# UKHASnet-avr-sensor.net
KiCad netlist of a schematic drawn in EAGLE
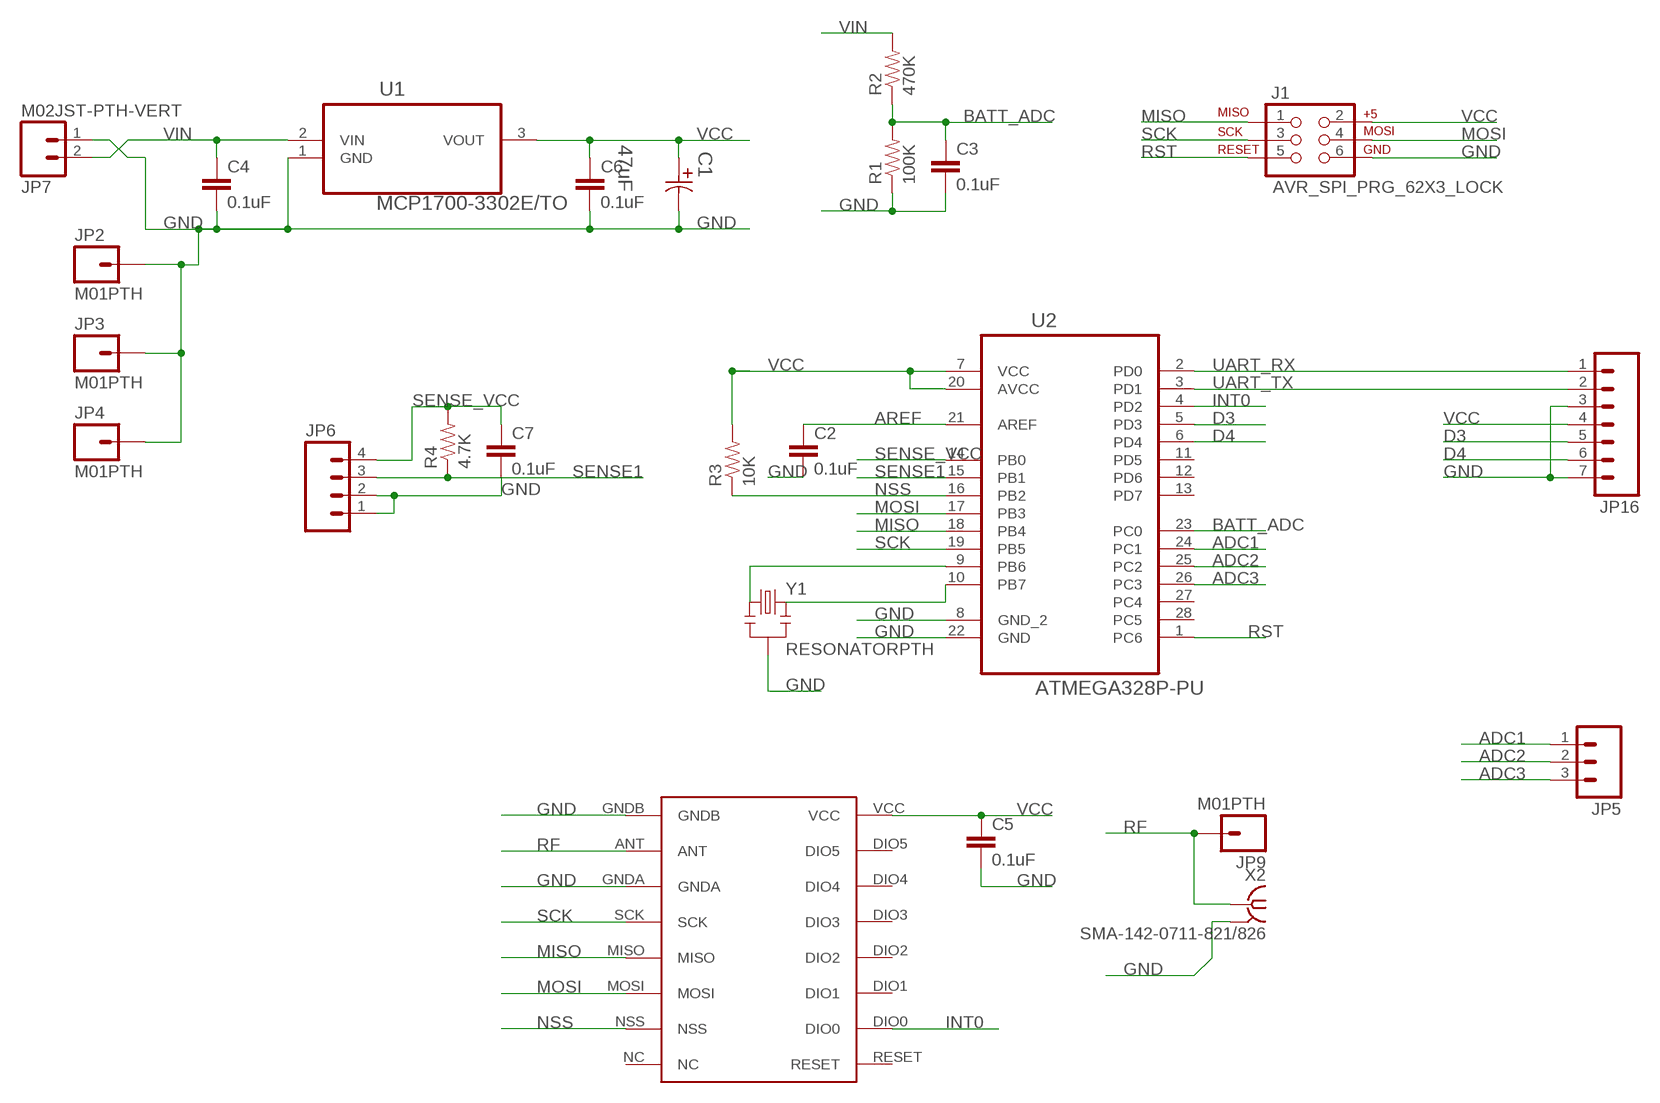
[diagram p0: schematic, sheet 1]

(export (version "E")
  (design (tool "Eeschema 10.0.6"))
  (components
    (comp (ref "C1")
      (value "47uF")
      (footprint "eagle-import:CAPPR150-400X1200")
      (fields (field (name "MPN") "EEUFC1J6R8") (field (name "TOLERANCE") "±20 %"))
      (libsource (lib "eagle-import") (part "EEU-P1.5FC1J6R8"))
    )
    (comp (ref "C2")
      (value "0.1uF")
      (footprint "eagle-import:C2.5-2")
      (libsource (lib "eagle-import") (part "C2.5/2"))
    )
    (comp (ref "C3")
      (value "0.1uF")
      (footprint "eagle-import:C2.5-2")
      (libsource (lib "eagle-import") (part "C2.5/2"))
    )
    (comp (ref "C4")
      (value "0.1uF")
      (footprint "eagle-import:C2.5-2")
      (libsource (lib "eagle-import") (part "C2.5/2"))
    )
    (comp (ref "C5")
      (value "0.1uF")
      (footprint "eagle-import:C2.5-2")
      (libsource (lib "eagle-import") (part "C2.5/2"))
    )
    (comp (ref "C6")
      (value "0.1uF")
      (footprint "eagle-import:C2.5-2")
      (libsource (lib "eagle-import") (part "C2.5/2"))
    )
    (comp (ref "C7")
      (value "0.1uF")
      (footprint "eagle-import:C2.5-2")
      (libsource (lib "eagle-import") (part "C2.5/2"))
    )
    (comp (ref "J1")
      (value "AVR_SPI_PRG_62X3_LOCK")
      (footprint "eagle-import:2X3_LOCK")
      (libsource (lib "eagle-import") (part "AVR_SPI_PRG_62X3_LOCK"))
    )
    (comp (ref "JP2")
      (value "M01PTH")
      (footprint "eagle-import:1X01")
      (libsource (lib "eagle-import") (part "M01PTH"))
    )
    (comp (ref "JP3")
      (value "M01PTH")
      (footprint "eagle-import:1X01")
      (libsource (lib "eagle-import") (part "M01PTH"))
    )
    (comp (ref "JP4")
      (value "M01PTH")
      (footprint "eagle-import:1X01")
      (libsource (lib "eagle-import") (part "M01PTH"))
    )
    (comp (ref "JP5")
      (value "M03PTH")
      (footprint "eagle-import:1X03")
      (libsource (lib "eagle-import") (part "M03PTH"))
    )
    (comp (ref "JP6")
      (value "M04PTH")
      (footprint "eagle-import:1X04")
      (libsource (lib "eagle-import") (part "M04PTH"))
    )
    (comp (ref "JP7")
      (value "M02JST-PTH-VERT")
      (footprint "eagle-import:JST-2-PTH-VERT")
      (libsource (lib "eagle-import") (part "M02JST-PTH-VERT"))
    )
    (comp (ref "JP9")
      (value "M01PTH")
      (footprint "eagle-import:1X01")
      (libsource (lib "eagle-import") (part "M01PTH"))
    )
    (comp (ref "JP16")
      (value "M07")
      (footprint "eagle-import:1X07")
      (libsource (lib "eagle-import") (part "M07"))
    )
    (comp (ref "R1")
      (value "100K")
      (footprint "eagle-import:AXIAL-0.4")
      (libsource (lib "eagle-import") (part "RESISTORPTH-1/4W"))
    )
    (comp (ref "R2")
      (value "470K")
      (footprint "eagle-import:AXIAL-0.4")
      (libsource (lib "eagle-import") (part "RESISTORPTH-1/4W"))
    )
    (comp (ref "R3")
      (value "10K")
      (footprint "eagle-import:AXIAL-0.4")
      (libsource (lib "eagle-import") (part "RESISTORPTH-1/4W"))
    )
    (comp (ref "R4")
      (value "4.7K")
      (footprint "eagle-import:AXIAL-0.4")
      (libsource (lib "eagle-import") (part "RESISTORPTH-1/4W"))
    )
    (comp (ref "U$1")
      (value "RFM69HW")
      (footprint "eagle-import:RFM")
      (libsource (lib "eagle-import") (part "RFM69HW"))
    )
    (comp (ref "U1")
      (value "MCP1700-3302E/TO")
      (footprint "eagle-import:TO127P254X495-3")
      (libsource (lib "eagle-import") (part "MCP1700-3302E/TO"))
    )
    (comp (ref "U2")
      (value "ATMEGA328P-PU")
      (footprint "eagle-import:DIP254P762X457-28")
      (libsource (lib "eagle-import") (part "ATMEGA328P-PU"))
    )
    (comp (ref "X2")
      (value "SMA-142-0711-821/826")
      (footprint "eagle-import:J502-ND-142-0711-821_826")
      (fields (field (name "MF") "JOHNSON COMPONENTS") (field (name "MPN") "142-0711-821"))
      (libsource (lib "eagle-import") (part "SMA-142-0711-821/826"))
    )
    (comp (ref "Y1")
      (value "RESONATORPTH")
      (footprint "eagle-import:RESONATOR-PTH")
      (libsource (lib "eagle-import") (part "RESONATORPTH"))
    )
  )
  (nets
    (net (code "1") (name "/ADC1") (class "Default")
      (node (ref "JP5") (pin "1") (pinfunction "1_1") (pintype "passive"))
      (node (ref "U2") (pin "24") (pinfunction "PC1_24") (pintype "bidirectional"))
    )
    (net (code "2") (name "/ADC2") (class "Default")
      (node (ref "JP5") (pin "2") (pinfunction "2_2") (pintype "passive"))
      (node (ref "U2") (pin "25") (pinfunction "PC2_25") (pintype "bidirectional"))
    )
    (net (code "3") (name "/ADC3") (class "Default")
      (node (ref "JP5") (pin "3") (pinfunction "3_3") (pintype "passive"))
      (node (ref "U2") (pin "26") (pinfunction "PC3_26") (pintype "bidirectional"))
    )
    (net (code "4") (name "/AREF") (class "Default")
      (node (ref "C2") (pin "1") (pinfunction "1_1") (pintype "passive"))
      (node (ref "U2") (pin "21") (pinfunction "AREF_21") (pintype "input"))
    )
    (net (code "5") (name "/BATT_ADC") (class "Default")
      (node (ref "C3") (pin "1") (pinfunction "1_1") (pintype "passive"))
      (node (ref "R1") (pin "P$2") (pinfunction "2_P$2") (pintype "passive"))
      (node (ref "R2") (pin "P$1") (pinfunction "1_P$1") (pintype "passive"))
      (node (ref "U2") (pin "23") (pinfunction "PC0_23") (pintype "bidirectional"))
    )
    (net (code "6") (name "/D3") (class "Default")
      (node (ref "JP16") (pin "5") (pinfunction "5_5") (pintype "passive"))
      (node (ref "U2") (pin "5") (pinfunction "PD3_5") (pintype "bidirectional"))
    )
    (net (code "7") (name "/D4") (class "Default")
      (node (ref "JP16") (pin "6") (pinfunction "6_6") (pintype "passive"))
      (node (ref "U2") (pin "6") (pinfunction "PD4_6") (pintype "bidirectional"))
    )
    (net (code "8") (name "/GND") (class "Default")
      (node (ref "C1") (pin "2") (pinfunction "2_2") (pintype "passive"))
      (node (ref "C2") (pin "2") (pinfunction "2_2") (pintype "passive"))
      (node (ref "C3") (pin "2") (pinfunction "2_2") (pintype "passive"))
      (node (ref "C4") (pin "2") (pinfunction "2_2") (pintype "passive"))
      (node (ref "C5") (pin "2") (pinfunction "2_2") (pintype "passive"))
      (node (ref "C6") (pin "2") (pinfunction "2_2") (pintype "passive"))
      (node (ref "C7") (pin "2") (pinfunction "2_2") (pintype "passive"))
      (node (ref "J1") (pin "6") (pinfunction "6_6") (pintype "passive"))
      (node (ref "JP16") (pin "3") (pinfunction "3_3") (pintype "passive"))
      (node (ref "JP16") (pin "7") (pinfunction "7_7") (pintype "passive"))
      (node (ref "JP2") (pin "1") (pinfunction "1_1") (pintype "passive"))
      (node (ref "JP3") (pin "1") (pinfunction "1_1") (pintype "passive"))
      (node (ref "JP4") (pin "1") (pinfunction "1_1") (pintype "passive"))
      (node (ref "JP6") (pin "1") (pinfunction "1_1") (pintype "passive"))
      (node (ref "JP6") (pin "2") (pinfunction "2_2") (pintype "passive"))
      (node (ref "JP7") (pin "1") (pinfunction "1_1") (pintype "passive"))
      (node (ref "R1") (pin "P$1") (pinfunction "1_P$1") (pintype "passive"))
      (node (ref "U$1") (pin "GNDA") (pinfunction "GNDA_GNDA") (pintype "bidirectional"))
      (node (ref "U$1") (pin "GNDB") (pinfunction "GNDB_GNDB") (pintype "bidirectional"))
      (node (ref "U1") (pin "1") (pinfunction "GND_1") (pintype "passive"))
      (node (ref "U2") (pin "22") (pinfunction "GND_22") (pintype "passive"))
      (node (ref "U2") (pin "8") (pinfunction "GND_2_8") (pintype "passive"))
      (node (ref "X2") (pin "G@1") (pinfunction "2_G@1") (pintype "passive"))
      (node (ref "X2") (pin "G@2") (pinfunction "2_G@2") (pintype "passive"))
      (node (ref "X2") (pin "G@3") (pinfunction "2_G@3") (pintype "passive"))
      (node (ref "X2") (pin "G@4") (pinfunction "2_G@4") (pintype "passive"))
      (node (ref "Y1") (pin "2") (pinfunction "2_2") (pintype "passive"))
    )
    (net (code "9") (name "/INT0") (class "Default")
      (node (ref "U$1") (pin "DIO0") (pinfunction "DIO0_DIO0") (pintype "bidirectional"))
      (node (ref "U2") (pin "4") (pinfunction "PD2_4") (pintype "bidirectional"))
    )
    (net (code "10") (name "/MISO") (class "Default")
      (node (ref "J1") (pin "1") (pinfunction "1_1") (pintype "passive"))
      (node (ref "U$1") (pin "MISO") (pinfunction "MISO_MISO") (pintype "bidirectional"))
      (node (ref "U2") (pin "18") (pinfunction "PB4_18") (pintype "bidirectional"))
    )
    (net (code "11") (name "/MOSI") (class "Default")
      (node (ref "J1") (pin "4") (pinfunction "4_4") (pintype "passive"))
      (node (ref "U$1") (pin "MOSI") (pinfunction "MOSI_MOSI") (pintype "bidirectional"))
      (node (ref "U2") (pin "17") (pinfunction "PB3_17") (pintype "bidirectional"))
    )
    (net (code "12") (name "/NSS") (class "Default")
      (node (ref "R3") (pin "P$1") (pinfunction "1_P$1") (pintype "passive"))
      (node (ref "U$1") (pin "NSS") (pinfunction "NSS_NSS") (pintype "bidirectional"))
      (node (ref "U2") (pin "16") (pinfunction "PB2_16") (pintype "bidirectional"))
    )
    (net (code "13") (name "/RF") (class "Default")
      (node (ref "JP9") (pin "1") (pinfunction "1_1") (pintype "passive"))
      (node (ref "U$1") (pin "ANT") (pinfunction "ANT_ANT") (pintype "bidirectional"))
      (node (ref "X2") (pin "1") (pinfunction "1_1") (pintype "passive"))
    )
    (net (code "14") (name "/RST") (class "Default")
      (node (ref "J1") (pin "5") (pinfunction "5_5") (pintype "passive"))
      (node (ref "U2") (pin "1") (pinfunction "PC6_1") (pintype "bidirectional"))
    )
    (net (code "15") (name "/SCK") (class "Default")
      (node (ref "J1") (pin "3") (pinfunction "3_3") (pintype "passive"))
      (node (ref "U$1") (pin "SCK") (pinfunction "SCK_SCK") (pintype "bidirectional"))
      (node (ref "U2") (pin "19") (pinfunction "PB5_19") (pintype "bidirectional"))
    )
    (net (code "16") (name "/SENSE1") (class "Default")
      (node (ref "JP6") (pin "3") (pinfunction "3_3") (pintype "passive"))
      (node (ref "R4") (pin "P$1") (pinfunction "1_P$1") (pintype "passive"))
      (node (ref "U2") (pin "15") (pinfunction "PB1_15") (pintype "bidirectional"))
    )
    (net (code "17") (name "/SENSE_VCC") (class "Default")
      (node (ref "C7") (pin "1") (pinfunction "1_1") (pintype "passive"))
      (node (ref "JP6") (pin "4") (pinfunction "4_4") (pintype "passive"))
      (node (ref "R4") (pin "P$2") (pinfunction "2_P$2") (pintype "passive"))
      (node (ref "U2") (pin "14") (pinfunction "PB0_14") (pintype "bidirectional"))
    )
    (net (code "18") (name "/UART_RX") (class "Default")
      (node (ref "JP16") (pin "1") (pinfunction "1_1") (pintype "passive"))
      (node (ref "U2") (pin "2") (pinfunction "PD0_2") (pintype "bidirectional"))
    )
    (net (code "19") (name "/UART_TX") (class "Default")
      (node (ref "JP16") (pin "2") (pinfunction "2_2") (pintype "passive"))
      (node (ref "U2") (pin "3") (pinfunction "PD1_3") (pintype "bidirectional"))
    )
    (net (code "20") (name "/VCC") (class "Default")
      (node (ref "C1") (pin "1") (pinfunction "1_1") (pintype "passive"))
      (node (ref "C5") (pin "1") (pinfunction "1_1") (pintype "passive"))
      (node (ref "C6") (pin "1") (pinfunction "1_1") (pintype "passive"))
      (node (ref "J1") (pin "2") (pinfunction "2_2") (pintype "passive"))
      (node (ref "JP16") (pin "4") (pinfunction "4_4") (pintype "passive"))
      (node (ref "R3") (pin "P$2") (pinfunction "2_P$2") (pintype "passive"))
      (node (ref "U$1") (pin "VCC") (pinfunction "VCC_VCC") (pintype "bidirectional"))
      (node (ref "U1") (pin "3") (pinfunction "VOUT_3") (pintype "output"))
      (node (ref "U2") (pin "20") (pinfunction "AVCC_20") (pintype "power_in"))
      (node (ref "U2") (pin "7") (pinfunction "VCC_7") (pintype "power_in"))
    )
    (net (code "21") (name "/VIN") (class "Default")
      (node (ref "C4") (pin "1") (pinfunction "1_1") (pintype "passive"))
      (node (ref "JP7") (pin "2") (pinfunction "2_2") (pintype "passive"))
      (node (ref "R2") (pin "P$2") (pinfunction "2_P$2") (pintype "passive"))
      (node (ref "U1") (pin "2") (pinfunction "VIN_2") (pintype "input"))
    )
    (net (code "22") (name "Net-(U2-PB6)") (class "Default")
      (node (ref "U2") (pin "9") (pinfunction "PB6_9") (pintype "bidirectional"))
      (node (ref "Y1") (pin "1") (pinfunction "1_1") (pintype "passive"))
    )
    (net (code "23") (name "Net-(U2-PB7)") (class "Default")
      (node (ref "U2") (pin "10") (pinfunction "PB7_10") (pintype "bidirectional"))
      (node (ref "Y1") (pin "3") (pinfunction "3_3") (pintype "passive"))
    )
    (net (code "24") (name "unconnected-(U$1-PadDIO1)") (class "Default")
      (node (ref "U$1") (pin "DIO1") (pinfunction "DIO1_DIO1") (pintype "bidirectional"))
    )
    (net (code "25") (name "unconnected-(U$1-PadDIO2)") (class "Default")
      (node (ref "U$1") (pin "DIO2") (pinfunction "DIO2_DIO2") (pintype "bidirectional"))
    )
    (net (code "26") (name "unconnected-(U$1-PadDIO3)") (class "Default")
      (node (ref "U$1") (pin "DIO3") (pinfunction "DIO3_DIO3") (pintype "bidirectional"))
    )
    (net (code "27") (name "unconnected-(U$1-PadDIO4)") (class "Default")
      (node (ref "U$1") (pin "DIO4") (pinfunction "DIO4_DIO4") (pintype "bidirectional"))
    )
    (net (code "28") (name "unconnected-(U$1-PadDIO5)") (class "Default")
      (node (ref "U$1") (pin "DIO5") (pinfunction "DIO5_DIO5") (pintype "bidirectional"))
    )
    (net (code "29") (name "unconnected-(U$1-PadNC)") (class "Default")
      (node (ref "U$1") (pin "NC") (pinfunction "NC_NC") (pintype "bidirectional"))
    )
    (net (code "30") (name "unconnected-(U$1-PadRESET)") (class "Default")
      (node (ref "U$1") (pin "RESET") (pinfunction "RESET_RESET") (pintype "bidirectional"))
    )
    (net (code "31") (name "unconnected-(U2-PC4-Pad27)") (class "Default")
      (node (ref "U2") (pin "27") (pinfunction "PC4_27") (pintype "bidirectional"))
    )
    (net (code "32") (name "unconnected-(U2-PC5-Pad28)") (class "Default")
      (node (ref "U2") (pin "28") (pinfunction "PC5_28") (pintype "bidirectional"))
    )
    (net (code "33") (name "unconnected-(U2-PD5-Pad11)") (class "Default")
      (node (ref "U2") (pin "11") (pinfunction "PD5_11") (pintype "bidirectional"))
    )
    (net (code "34") (name "unconnected-(U2-PD6-Pad12)") (class "Default")
      (node (ref "U2") (pin "12") (pinfunction "PD6_12") (pintype "bidirectional"))
    )
    (net (code "35") (name "unconnected-(U2-PD7-Pad13)") (class "Default")
      (node (ref "U2") (pin "13") (pinfunction "PD7_13") (pintype "bidirectional"))
    )
  )
)
